# Flyfocus_Bird_CANdy_V1_0.net
KiCad netlist of a schematic drawn in EAGLE
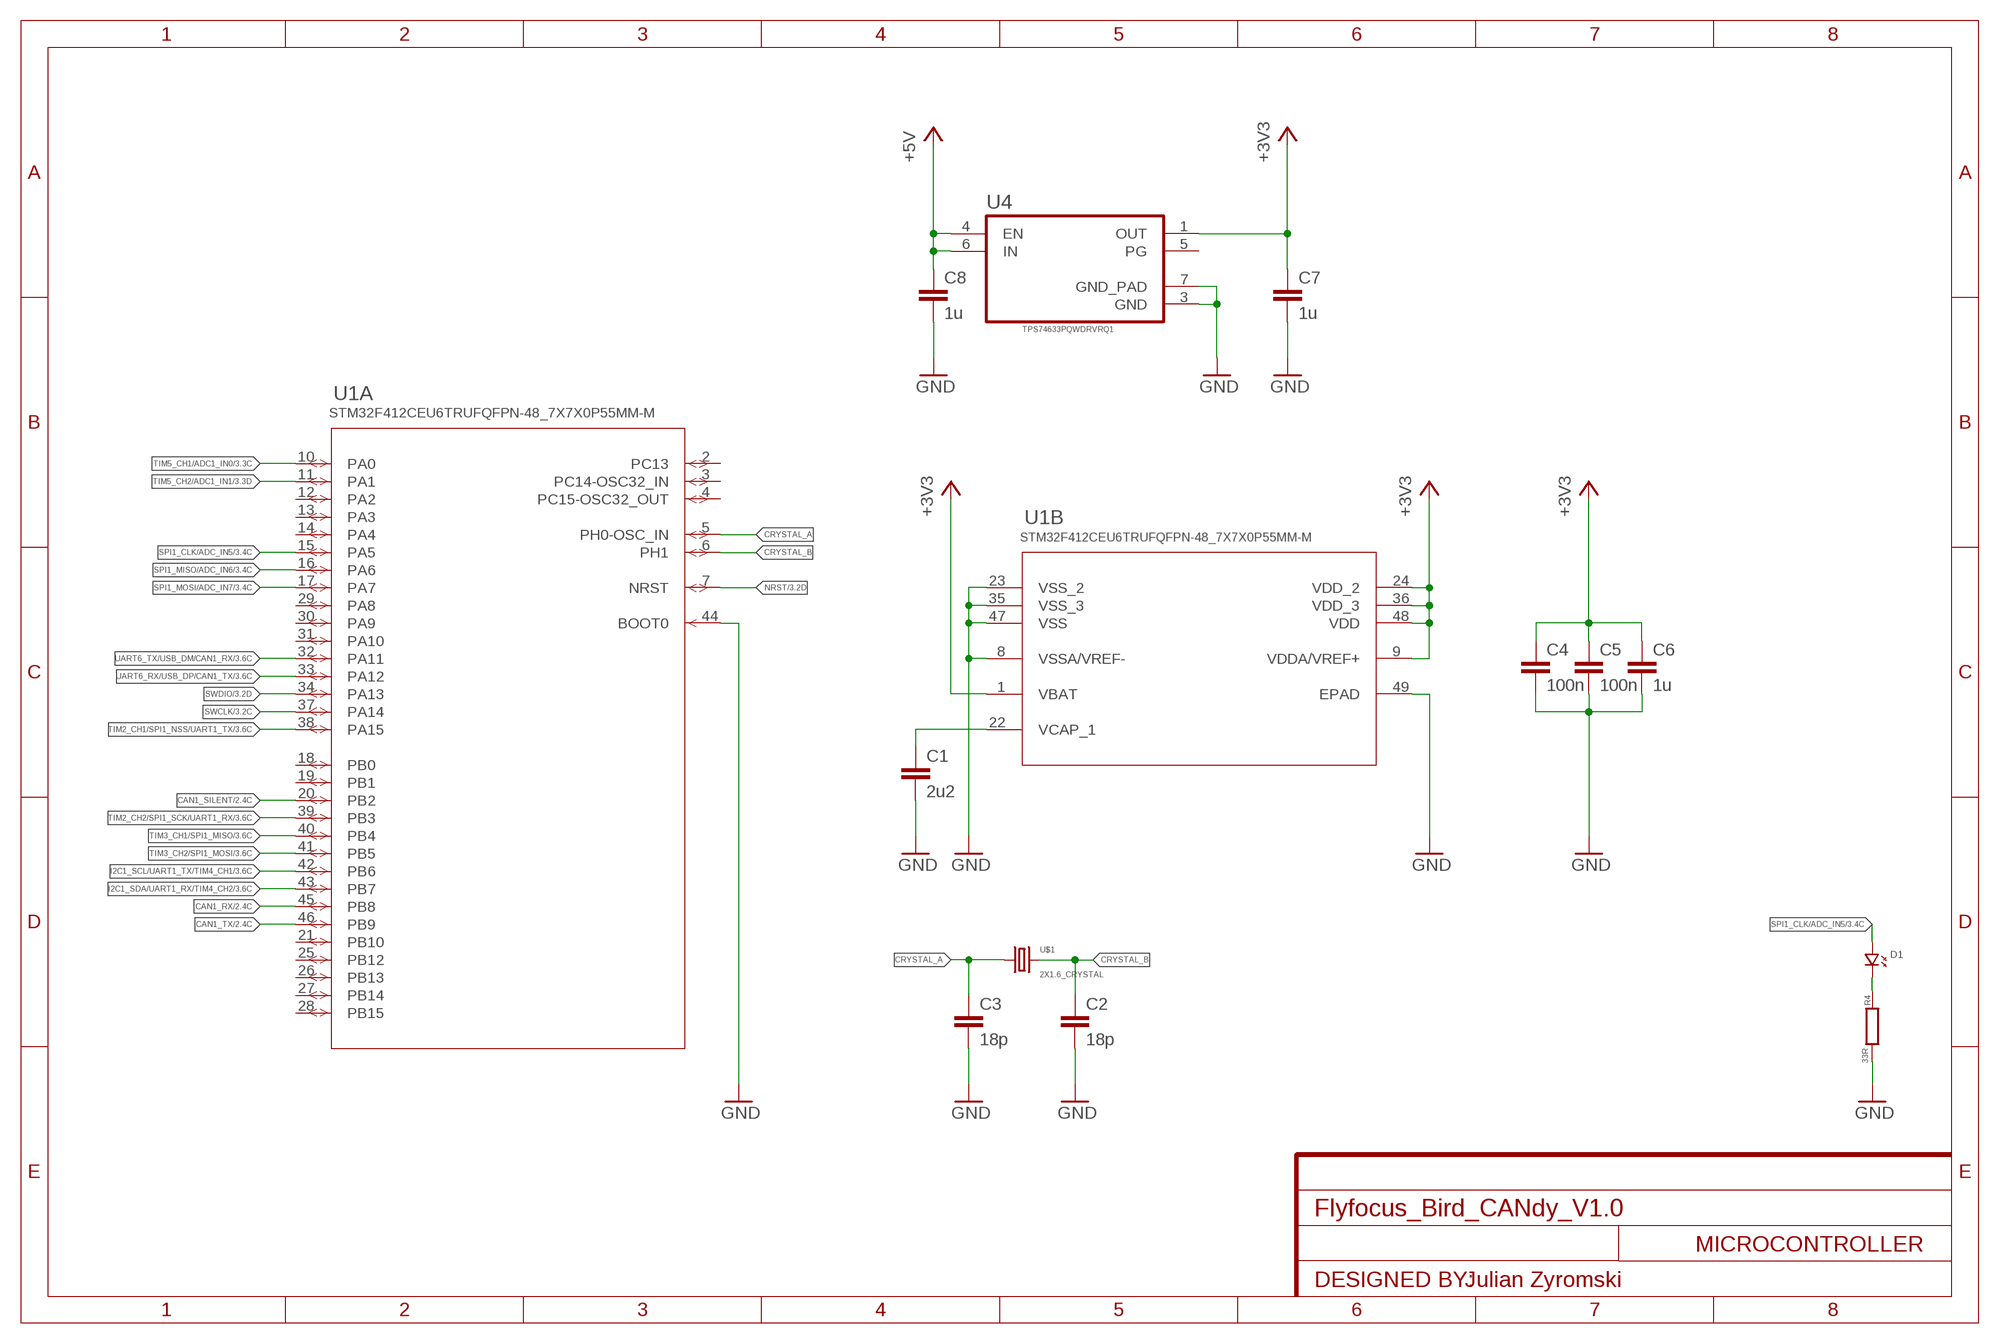
[diagram p0: schematic, sheet 1]
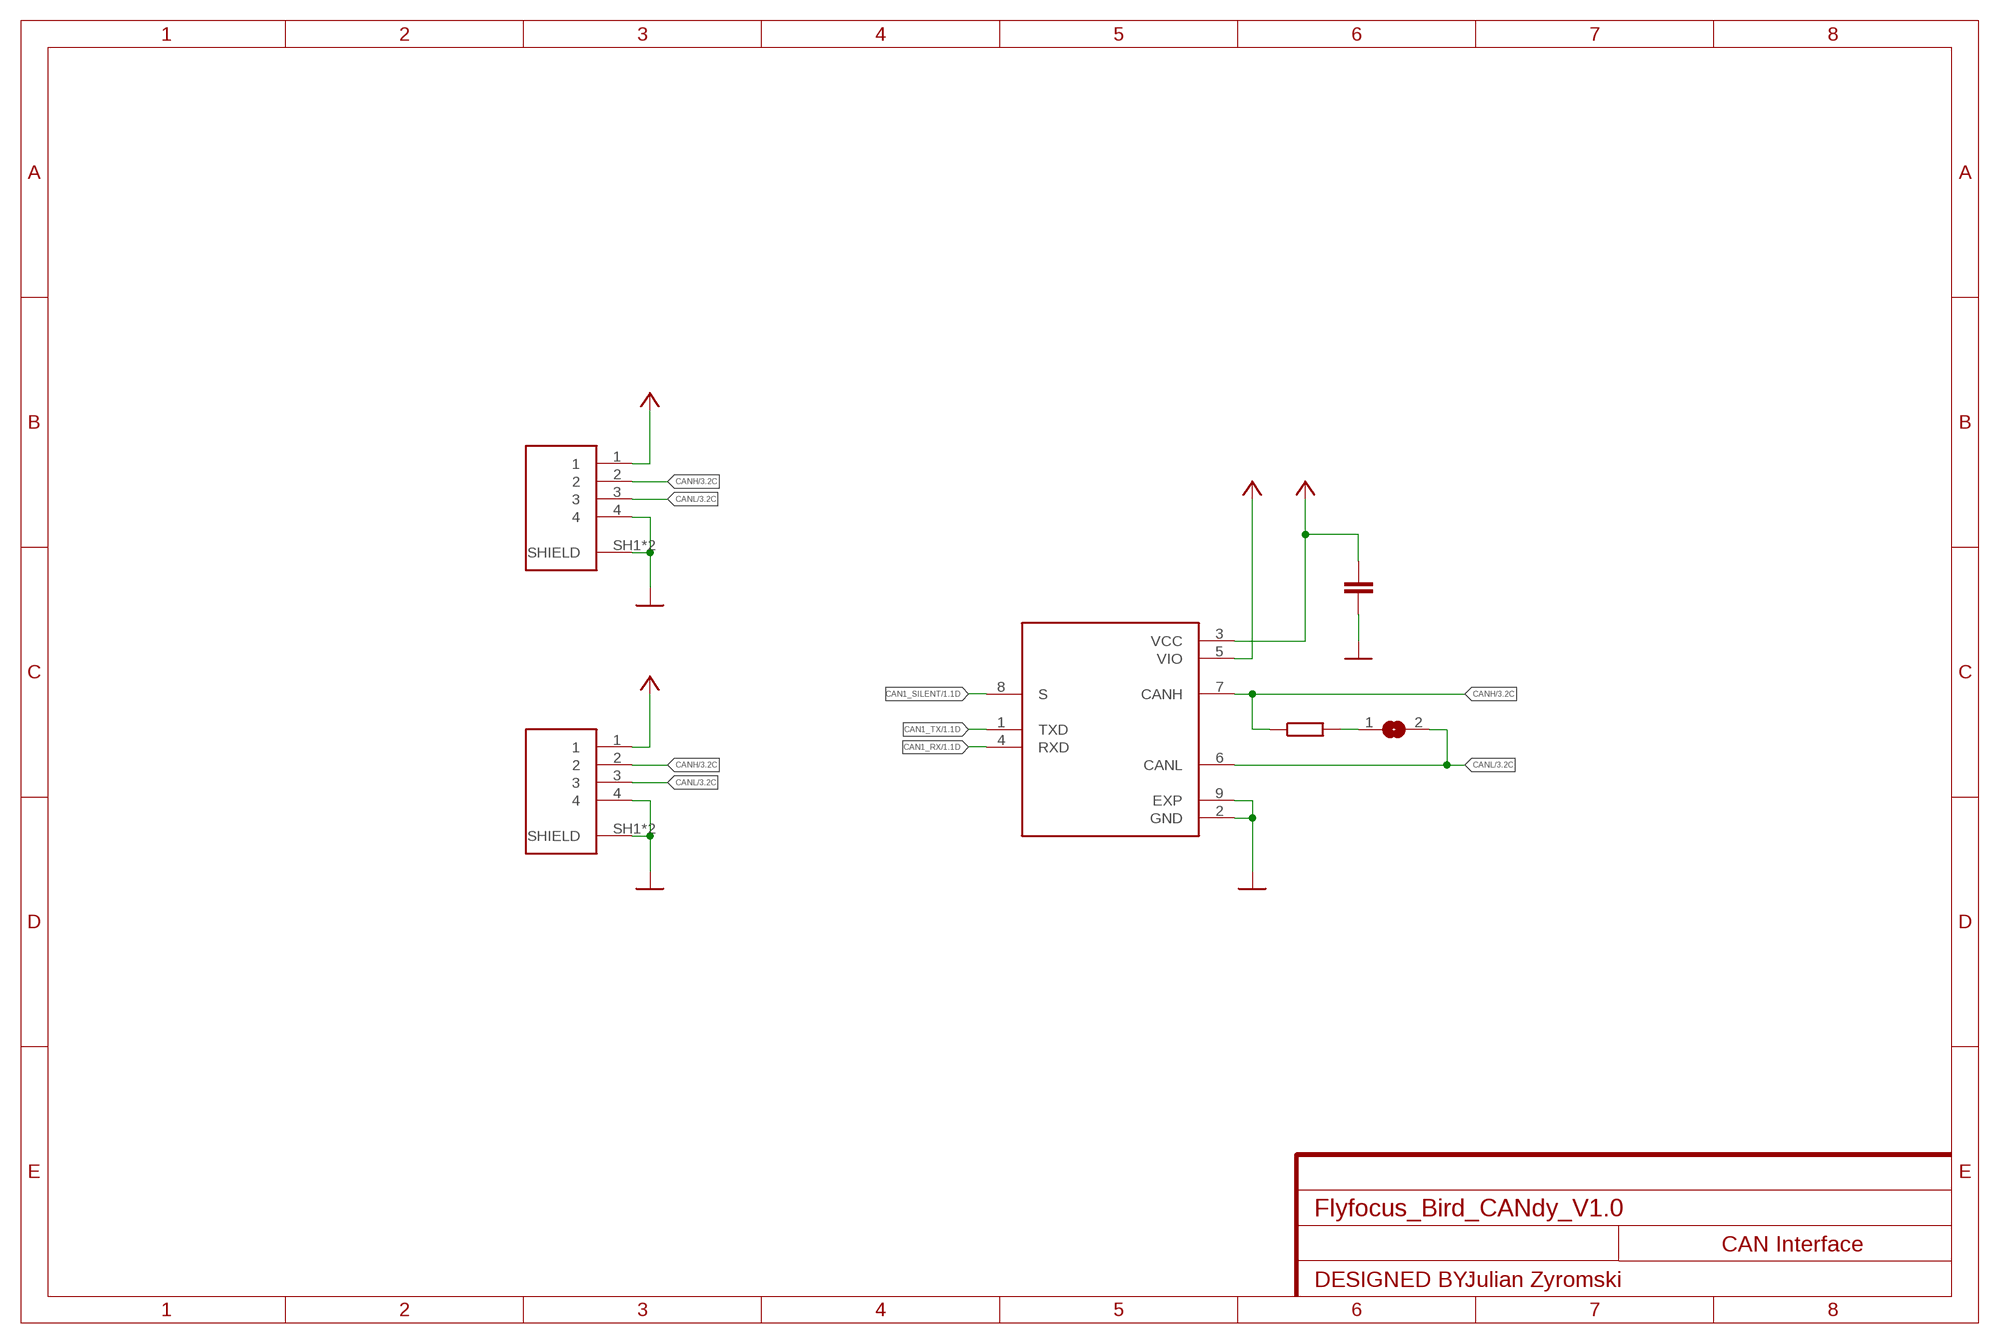
[diagram p1: schematic, sheet 2]
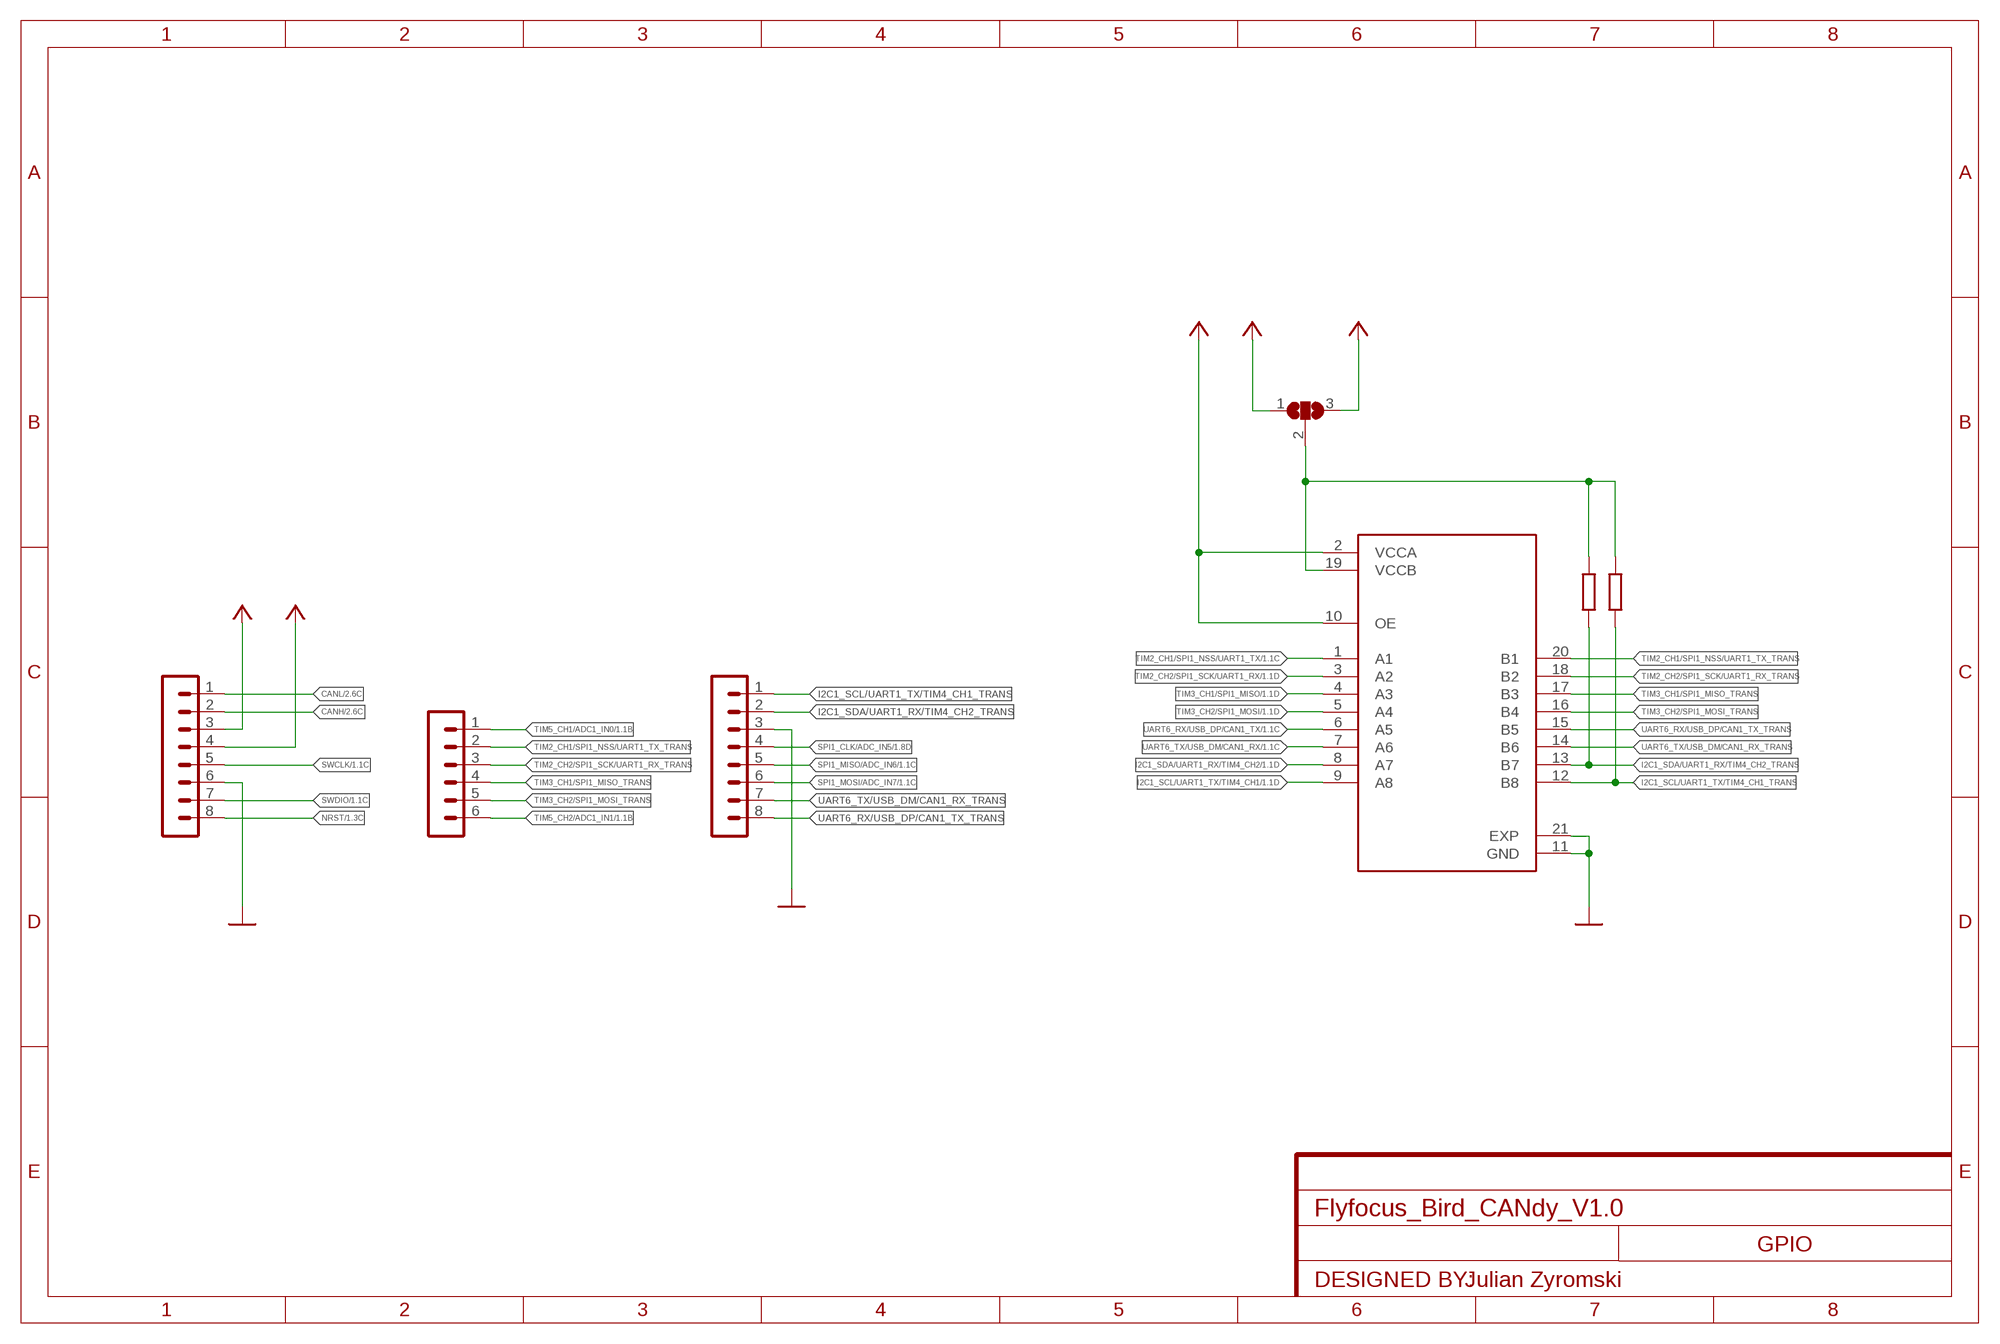
[diagram p2: schematic, sheet 3]

(export (version "E")
  (design (tool "Eeschema 10.0.6"))
  (components
    (comp (ref "C1")
      (value "2u2")
      (footprint "eagle-import:R0402")
      (libsource (lib "eagle-import") (part "C-EUC0402_RESISTOR_FOOTPRINT"))
    )
    (comp (ref "C2")
      (value "18p")
      (footprint "eagle-import:R0402")
      (libsource (lib "eagle-import") (part "C-EUC0402_RESISTOR_FOOTPRINT"))
    )
    (comp (ref "C3")
      (value "18p")
      (footprint "eagle-import:R0402")
      (libsource (lib "eagle-import") (part "C-EUC0402_RESISTOR_FOOTPRINT"))
    )
    (comp (ref "C4")
      (value "100n")
      (footprint "eagle-import:R0402")
      (libsource (lib "eagle-import") (part "C-EUC0402_RESISTOR_FOOTPRINT"))
    )
    (comp (ref "C5")
      (value "100n")
      (footprint "eagle-import:R0402")
      (libsource (lib "eagle-import") (part "C-EUC0402_RESISTOR_FOOTPRINT"))
    )
    (comp (ref "C6")
      (value "1u")
      (footprint "eagle-import:R0402")
      (libsource (lib "eagle-import") (part "C-EUC0402_RESISTOR_FOOTPRINT"))
    )
    (comp (ref "C7")
      (value "1u")
      (footprint "eagle-import:R0402")
      (libsource (lib "eagle-import") (part "C-EUC0402_RESISTOR_FOOTPRINT"))
    )
    (comp (ref "C8")
      (value "1u")
      (footprint "eagle-import:R0402")
      (libsource (lib "eagle-import") (part "C-EUC0402_RESISTOR_FOOTPRINT"))
    )
    (comp (ref "D1")
      (value "LED.0402")
      (footprint "eagle-import:0402.LED")
      (libsource (lib "eagle-import") (part "LED.0402"))
    )
    (comp (ref "R4")
      (value "33R")
      (footprint "eagle-import:R0402")
      (libsource (lib "eagle-import") (part "R-EU_R0402"))
    )
    (comp (ref "U$1")
      (value "2X1.6_CRYSTAL")
      (footprint "eagle-import:OSC_FA-128_16MHZ")
      (libsource (lib "eagle-import") (part "2X1.6_CRYSTAL"))
    )
    (comp (ref "U1")
      (value "STM32F412CEU6TRUFQFPN-48_7X7X0P55MM-M")
      (footprint "eagle-import:UFQFPN-48_7X7X0P55MM-M")
      (fields
        (field (name "MANUFACTURER_PART_NUMBER") "STM32F412CEU6TR")
        (field (name "COPYRIGHT") "Copyright (C) 2018 Accelerated Designs. All rights reserved")
      )
      (libsource (lib "eagle-import") (part "STM32F412CEU6TRUFQFPN-48_7X7X0P55MM-M"))
    )
    (comp (ref "U4")
      (value "TPS74633PQWDRVRQ1")
      (footprint "eagle-import:SON65P200X200X80-7N")
      (fields (field (name "MF") "Texas Instruments"))
      (libsource (lib "eagle-import") (part "TPS74633PQWDRVRQ1"))
    )
    (comp (ref "R2")
      (value "4k7")
      (footprint "eagle-import:R0402")
      (libsource (lib "eagle-import") (part "R-EU_R0402"))
    )
    (comp (ref "R3")
      (value "4k7")
      (footprint "eagle-import:R0402")
      (libsource (lib "eagle-import") (part "R-EU_R0402"))
    )
    (comp (ref "SJ2")
      (value "SJ2W")
      (footprint "eagle-import:SJ_2")
      (libsource (lib "eagle-import") (part "SJ2W"))
    )
    (comp (ref "SV1")
      (value "MA08-1")
      (footprint "eagle-import:MA08-1")
      (libsource (lib "eagle-import") (part "MA08-1"))
    )
    (comp (ref "SV2")
      (value "MA08-1")
      (footprint "eagle-import:MA08-1")
      (libsource (lib "eagle-import") (part "MA08-1"))
    )
    (comp (ref "SV3")
      (value "MA06-1")
      (footprint "eagle-import:MA06-1")
      (libsource (lib "eagle-import") (part "MA06-1"))
    )
    (comp (ref "U3")
      (value "TXS0108ERGYR")
      (footprint "eagle-import:IC_TXS0108ERGYR")
      (fields (field (name "MF") "Texas Instruments"))
      (libsource (lib "eagle-import") (part "TXS0108ERGYR"))
    )
    (comp (ref "C9")
      (value "2u2")
      (footprint "eagle-import:R0402")
      (libsource (lib "eagle-import") (part "C-EUC0402_RESISTOR_FOOTPRINT"))
    )
    (comp (ref "J1")
      (value "SM04B-GHS-TB(LF)(SN)-")
      (footprint "eagle-import:JST_SM04B-GHS-TB(LF)(SN)-")
      (fields (field (name "MF") "JST Sales") (field (name "MP") "SM04B-GHS-TB_LF__SN_-"))
      (libsource (lib "eagle-import") (part "SM04B-GHS-TB(LF)(SN)-"))
    )
    (comp (ref "J2")
      (value "SM04B-GHS-TB(LF)(SN)-")
      (footprint "eagle-import:JST_SM04B-GHS-TB(LF)(SN)-")
      (fields (field (name "MF") "JST Sales") (field (name "MP") "SM04B-GHS-TB_LF__SN_-"))
      (libsource (lib "eagle-import") (part "SM04B-GHS-TB(LF)(SN)-"))
    )
    (comp (ref "R1")
      (value "120R/thick_film")
      (footprint "eagle-import:0603")
      (libsource (lib "eagle-import") (part "R0603"))
    )
    (comp (ref "SJ1") (value "SJ") (footprint "eagle-import:SJ") (libsource (lib "eagle-import") (part "SJ")))
    (comp (ref "U2")
      (value "TJA1051TK/3/1J")
      (footprint "eagle-import:SON65P300X300X95-8N")
      (fields (field (name "MF") "NXP USA"))
      (libsource (lib "eagle-import") (part "TJA1051TK/3/1J"))
    )
  )
  (nets
    (net (code "1") (name "+3V3") (class "Default")
      (node (ref "C4") (pin "1") (pinfunction "1_1") (pintype "passive"))
      (node (ref "C5") (pin "1") (pinfunction "1_1") (pintype "passive"))
      (node (ref "C6") (pin "1") (pinfunction "1_1") (pintype "passive"))
      (node (ref "C7") (pin "1") (pinfunction "1_1") (pintype "passive"))
      (node (ref "SJ2") (pin "1") (pinfunction "1_1") (pintype "passive"))
      (node (ref "SV1") (pin "4") (pinfunction "4_4") (pintype "passive"))
      (node (ref "U1") (pin "1") (pinfunction "VBAT_1") (pintype "power_in"))
      (node (ref "U1") (pin "24") (pinfunction "VDD_2_24") (pintype "power_in"))
      (node (ref "U1") (pin "36") (pinfunction "VDD_3_36") (pintype "power_in"))
      (node (ref "U1") (pin "48") (pinfunction "VDD_48") (pintype "power_in"))
      (node (ref "U1") (pin "9") (pinfunction "VDDA/VREF+_9") (pintype "power_in"))
      (node (ref "U2") (pin "5") (pinfunction "VIO_5") (pintype "power_in"))
      (node (ref "U3") (pin "10") (pinfunction "OE_10") (pintype "input"))
      (node (ref "U3") (pin "2") (pinfunction "VCCA_2") (pintype "power_in"))
      (node (ref "U4") (pin "1") (pinfunction "OUT_1") (pintype "output"))
    )
    (net (code "2") (name "+5V") (class "Default")
      (node (ref "C8") (pin "1") (pinfunction "1_1") (pintype "passive"))
      (node (ref "C9") (pin "1") (pinfunction "1_1") (pintype "passive"))
      (node (ref "J1") (pin "1") (pinfunction "1_1") (pintype "passive"))
      (node (ref "J2") (pin "1") (pinfunction "1_1") (pintype "passive"))
      (node (ref "SJ2") (pin "3") (pinfunction "3_3") (pintype "passive"))
      (node (ref "SV1") (pin "3") (pinfunction "3_3") (pintype "passive"))
      (node (ref "U2") (pin "3") (pinfunction "VCC_3") (pintype "power_in"))
      (node (ref "U4") (pin "4") (pinfunction "EN_4") (pintype "input"))
      (node (ref "U4") (pin "6") (pinfunction "IN_6") (pintype "input"))
    )
    (net (code "3") (name "CAN1_RX") (class "Default")
      (node (ref "U1") (pin "45") (pinfunction "PB8_45") (pintype "bidirectional"))
      (node (ref "U2") (pin "4") (pinfunction "RXD_4") (pintype "output"))
    )
    (net (code "4") (name "CAN1_SILENT") (class "Default")
      (node (ref "U1") (pin "20") (pinfunction "PB2_20") (pintype "bidirectional"))
      (node (ref "U2") (pin "8") (pinfunction "S_8") (pintype "input"))
    )
    (net (code "5") (name "CAN1_TX") (class "Default")
      (node (ref "U1") (pin "46") (pinfunction "PB9_46") (pintype "bidirectional"))
      (node (ref "U2") (pin "1") (pinfunction "TXD_1") (pintype "input"))
    )
    (net (code "6") (name "CANH") (class "Default")
      (node (ref "J1") (pin "2") (pinfunction "2_2") (pintype "passive"))
      (node (ref "J2") (pin "2") (pinfunction "2_2") (pintype "passive"))
      (node (ref "R1") (pin "P$1") (pinfunction "1_P$1") (pintype "passive"))
      (node (ref "SV1") (pin "2") (pinfunction "2_2") (pintype "passive"))
      (node (ref "U2") (pin "7") (pinfunction "CANH_7") (pintype "bidirectional"))
    )
    (net (code "7") (name "CANL") (class "Default")
      (node (ref "J1") (pin "3") (pinfunction "3_3") (pintype "passive"))
      (node (ref "J2") (pin "3") (pinfunction "3_3") (pintype "passive"))
      (node (ref "SJ1") (pin "2") (pinfunction "2_2") (pintype "passive"))
      (node (ref "SV1") (pin "1") (pinfunction "1_1") (pintype "passive"))
      (node (ref "U2") (pin "6") (pinfunction "CANL_6") (pintype "bidirectional"))
    )
    (net (code "8") (name "CRYSTAL_A") (class "Default")
      (node (ref "C3") (pin "1") (pinfunction "1_1") (pintype "passive"))
      (node (ref "U$1") (pin "1") (pinfunction "1_1") (pintype "passive"))
      (node (ref "U1") (pin "5") (pinfunction "PH0-OSC_IN_5") (pintype "bidirectional"))
    )
    (net (code "9") (name "CRYSTAL_B") (class "Default")
      (node (ref "C2") (pin "1") (pinfunction "1_1") (pintype "passive"))
      (node (ref "U$1") (pin "3") (pinfunction "2_3") (pintype "passive"))
      (node (ref "U1") (pin "6") (pinfunction "PH1_6") (pintype "bidirectional"))
    )
    (net (code "10") (name "GND") (class "Default")
      (node (ref "C1") (pin "2") (pinfunction "2_2") (pintype "passive"))
      (node (ref "C2") (pin "2") (pinfunction "2_2") (pintype "passive"))
      (node (ref "C3") (pin "2") (pinfunction "2_2") (pintype "passive"))
      (node (ref "C4") (pin "2") (pinfunction "2_2") (pintype "passive"))
      (node (ref "C5") (pin "2") (pinfunction "2_2") (pintype "passive"))
      (node (ref "C6") (pin "2") (pinfunction "2_2") (pintype "passive"))
      (node (ref "C7") (pin "2") (pinfunction "2_2") (pintype "passive"))
      (node (ref "C8") (pin "2") (pinfunction "2_2") (pintype "passive"))
      (node (ref "C9") (pin "2") (pinfunction "2_2") (pintype "passive"))
      (node (ref "J1") (pin "4") (pinfunction "4_4") (pintype "passive"))
      (node (ref "J1") (pin "SH1") (pinfunction "SHIELD_SH1") (pintype "power_in"))
      (node (ref "J1") (pin "SH2") (pinfunction "SHIELD_SH2") (pintype "power_in"))
      (node (ref "J2") (pin "4") (pinfunction "4_4") (pintype "passive"))
      (node (ref "J2") (pin "SH1") (pinfunction "SHIELD_SH1") (pintype "power_in"))
      (node (ref "J2") (pin "SH2") (pinfunction "SHIELD_SH2") (pintype "power_in"))
      (node (ref "R4") (pin "2") (pinfunction "2_2") (pintype "passive"))
      (node (ref "SV1") (pin "6") (pinfunction "6_6") (pintype "passive"))
      (node (ref "SV2") (pin "3") (pinfunction "3_3") (pintype "passive"))
      (node (ref "U1") (pin "23") (pinfunction "VSS_2_23") (pintype "power_in"))
      (node (ref "U1") (pin "35") (pinfunction "VSS_3_35") (pintype "power_in"))
      (node (ref "U1") (pin "44") (pinfunction "BOOT0_44") (pintype "input"))
      (node (ref "U1") (pin "47") (pinfunction "VSS_47") (pintype "power_in"))
      (node (ref "U1") (pin "49") (pinfunction "EPAD_49") (pintype "passive"))
      (node (ref "U1") (pin "8") (pinfunction "VSSA/VREF-_8") (pintype "power_in"))
      (node (ref "U2") (pin "2") (pinfunction "GND_2") (pintype "power_in"))
      (node (ref "U2") (pin "9") (pinfunction "EXP_9") (pintype "power_in"))
      (node (ref "U3") (pin "11") (pinfunction "GND_11") (pintype "power_in"))
      (node (ref "U3") (pin "21") (pinfunction "EXP_21") (pintype "power_in"))
      (node (ref "U4") (pin "3") (pinfunction "GND_3") (pintype "power_in"))
      (node (ref "U4") (pin "7") (pinfunction "GND_PAD_7") (pintype "power_in"))
    )
    (net (code "11") (name "I2C1_SCL{slash}UART1_TX{slash}TIM4_CH1") (class "Default")
      (node (ref "U1") (pin "42") (pinfunction "PB6_42") (pintype "bidirectional"))
      (node (ref "U3") (pin "9") (pinfunction "A8_9") (pintype "bidirectional"))
    )
    (net (code "12") (name "I2C1_SCL{slash}UART1_TX{slash}TIM4_CH1_TRANS") (class "Default")
      (node (ref "R3") (pin "1") (pinfunction "1_1") (pintype "passive"))
      (node (ref "SV2") (pin "1") (pinfunction "1_1") (pintype "passive"))
      (node (ref "U3") (pin "12") (pinfunction "B8_12") (pintype "bidirectional"))
    )
    (net (code "13") (name "I2C1_SDA{slash}UART1_RX{slash}TIM4_CH2") (class "Default")
      (node (ref "U1") (pin "43") (pinfunction "PB7_43") (pintype "bidirectional"))
      (node (ref "U3") (pin "8") (pinfunction "A7_8") (pintype "bidirectional"))
    )
    (net (code "14") (name "I2C1_SDA{slash}UART1_RX{slash}TIM4_CH2_TRANS") (class "Default")
      (node (ref "R2") (pin "1") (pinfunction "1_1") (pintype "passive"))
      (node (ref "SV2") (pin "2") (pinfunction "2_2") (pintype "passive"))
      (node (ref "U3") (pin "13") (pinfunction "B7_13") (pintype "bidirectional"))
    )
    (net (code "15") (name "NRST") (class "Default")
      (node (ref "SV1") (pin "8") (pinfunction "8_8") (pintype "passive"))
      (node (ref "U1") (pin "7") (pinfunction "NRST_7") (pintype "bidirectional"))
    )
    (net (code "16") (name "Net-(D1-2)") (class "Default")
      (node (ref "D1") (pin "P$2") (pinfunction "2_P$2") (pintype "bidirectional"))
      (node (ref "R4") (pin "1") (pinfunction "1_1") (pintype "passive"))
    )
    (net (code "17") (name "Net-(R1-2)") (class "Default")
      (node (ref "R1") (pin "P$2") (pinfunction "2_P$2") (pintype "passive"))
      (node (ref "SJ1") (pin "1") (pinfunction "1_1") (pintype "passive"))
    )
    (net (code "18") (name "Net-(U1B-VCAP_1)") (class "Default")
      (node (ref "C1") (pin "1") (pinfunction "1_1") (pintype "passive"))
      (node (ref "U1") (pin "22") (pinfunction "VCAP_1_22") (pintype "power_in"))
    )
    (net (code "19") (name "Net-(U3-VCCB)") (class "Default")
      (node (ref "R2") (pin "2") (pinfunction "2_2") (pintype "passive"))
      (node (ref "R3") (pin "2") (pinfunction "2_2") (pintype "passive"))
      (node (ref "SJ2") (pin "2") (pinfunction "2_2") (pintype "passive"))
      (node (ref "U3") (pin "19") (pinfunction "VCCB_19") (pintype "power_in"))
    )
    (net (code "20") (name "SPI1_CLK{slash}ADC_IN5") (class "Default")
      (node (ref "D1") (pin "P$1") (pinfunction "1_P$1") (pintype "bidirectional"))
      (node (ref "SV2") (pin "4") (pinfunction "4_4") (pintype "passive"))
      (node (ref "U1") (pin "15") (pinfunction "PA5_15") (pintype "bidirectional"))
    )
    (net (code "21") (name "SPI1_MISO{slash}ADC_IN6") (class "Default")
      (node (ref "SV2") (pin "5") (pinfunction "5_5") (pintype "passive"))
      (node (ref "U1") (pin "16") (pinfunction "PA6_16") (pintype "bidirectional"))
    )
    (net (code "22") (name "SPI1_MOSI{slash}ADC_IN7") (class "Default")
      (node (ref "SV2") (pin "6") (pinfunction "6_6") (pintype "passive"))
      (node (ref "U1") (pin "17") (pinfunction "PA7_17") (pintype "bidirectional"))
    )
    (net (code "23") (name "SWCLK") (class "Default")
      (node (ref "SV1") (pin "5") (pinfunction "5_5") (pintype "passive"))
      (node (ref "U1") (pin "37") (pinfunction "PA14_37") (pintype "bidirectional"))
    )
    (net (code "24") (name "SWDIO") (class "Default")
      (node (ref "SV1") (pin "7") (pinfunction "7_7") (pintype "passive"))
      (node (ref "U1") (pin "34") (pinfunction "PA13_34") (pintype "bidirectional"))
    )
    (net (code "25") (name "TIM2_CH1{slash}SPI1_NSS{slash}UART1_TX") (class "Default")
      (node (ref "U1") (pin "38") (pinfunction "PA15_38") (pintype "bidirectional"))
      (node (ref "U3") (pin "1") (pinfunction "A1_1") (pintype "bidirectional"))
    )
    (net (code "26") (name "TIM2_CH1{slash}SPI1_NSS{slash}UART1_TX_TRANS") (class "Default")
      (node (ref "SV3") (pin "2") (pinfunction "2_2") (pintype "passive"))
      (node (ref "U3") (pin "20") (pinfunction "B1_20") (pintype "bidirectional"))
    )
    (net (code "27") (name "TIM2_CH2{slash}SPI1_SCK{slash}UART1_RX") (class "Default")
      (node (ref "U1") (pin "39") (pinfunction "PB3_39") (pintype "bidirectional"))
      (node (ref "U3") (pin "3") (pinfunction "A2_3") (pintype "bidirectional"))
    )
    (net (code "28") (name "TIM2_CH2{slash}SPI1_SCK{slash}UART1_RX_TRANS") (class "Default")
      (node (ref "SV3") (pin "3") (pinfunction "3_3") (pintype "passive"))
      (node (ref "U3") (pin "18") (pinfunction "B2_18") (pintype "bidirectional"))
    )
    (net (code "29") (name "TIM3_CH1{slash}SPI1_MISO") (class "Default")
      (node (ref "U1") (pin "40") (pinfunction "PB4_40") (pintype "bidirectional"))
      (node (ref "U3") (pin "4") (pinfunction "A3_4") (pintype "bidirectional"))
    )
    (net (code "30") (name "TIM3_CH1{slash}SPI1_MISO_TRANS") (class "Default")
      (node (ref "SV3") (pin "4") (pinfunction "4_4") (pintype "passive"))
      (node (ref "U3") (pin "17") (pinfunction "B3_17") (pintype "bidirectional"))
    )
    (net (code "31") (name "TIM3_CH2{slash}SPI1_MOSI") (class "Default")
      (node (ref "U1") (pin "41") (pinfunction "PB5_41") (pintype "bidirectional"))
      (node (ref "U3") (pin "5") (pinfunction "A4_5") (pintype "bidirectional"))
    )
    (net (code "32") (name "TIM3_CH2{slash}SPI1_MOSI_TRANS") (class "Default")
      (node (ref "SV3") (pin "5") (pinfunction "5_5") (pintype "passive"))
      (node (ref "U3") (pin "16") (pinfunction "B4_16") (pintype "bidirectional"))
    )
    (net (code "33") (name "TIM5_CH1{slash}ADC1_IN0") (class "Default")
      (node (ref "SV3") (pin "1") (pinfunction "1_1") (pintype "passive"))
      (node (ref "U1") (pin "10") (pinfunction "PA0_10") (pintype "bidirectional"))
    )
    (net (code "34") (name "TIM5_CH2{slash}ADC1_IN1") (class "Default")
      (node (ref "SV3") (pin "6") (pinfunction "6_6") (pintype "passive"))
      (node (ref "U1") (pin "11") (pinfunction "PA1_11") (pintype "bidirectional"))
    )
    (net (code "35") (name "UART6_RX{slash}USB_DP{slash}CAN1_TX") (class "Default")
      (node (ref "U1") (pin "33") (pinfunction "PA12_33") (pintype "bidirectional"))
      (node (ref "U3") (pin "6") (pinfunction "A5_6") (pintype "bidirectional"))
    )
    (net (code "36") (name "UART6_RX{slash}USB_DP{slash}CAN1_TX_TRANS") (class "Default")
      (node (ref "SV2") (pin "8") (pinfunction "8_8") (pintype "passive"))
      (node (ref "U3") (pin "15") (pinfunction "B5_15") (pintype "bidirectional"))
    )
    (net (code "37") (name "UART6_TX{slash}USB_DM{slash}CAN1_RX") (class "Default")
      (node (ref "U1") (pin "32") (pinfunction "PA11_32") (pintype "bidirectional"))
      (node (ref "U3") (pin "7") (pinfunction "A6_7") (pintype "bidirectional"))
    )
    (net (code "38") (name "UART6_TX{slash}USB_DM{slash}CAN1_RX_TRANS") (class "Default")
      (node (ref "SV2") (pin "7") (pinfunction "7_7") (pintype "passive"))
      (node (ref "U3") (pin "14") (pinfunction "B6_14") (pintype "bidirectional"))
    )
    (net (code "39") (name "unconnected-(U1A-PA2-Pad12)") (class "Default")
      (node (ref "U1") (pin "12") (pinfunction "PA2_12") (pintype "bidirectional"))
    )
    (net (code "40") (name "unconnected-(U1A-PA3-Pad13)") (class "Default")
      (node (ref "U1") (pin "13") (pinfunction "PA3_13") (pintype "bidirectional"))
    )
    (net (code "41") (name "unconnected-(U1A-PA4-Pad14)") (class "Default")
      (node (ref "U1") (pin "14") (pinfunction "PA4_14") (pintype "bidirectional"))
    )
    (net (code "42") (name "unconnected-(U1A-PA8-Pad29)") (class "Default")
      (node (ref "U1") (pin "29") (pinfunction "PA8_29") (pintype "bidirectional"))
    )
    (net (code "43") (name "unconnected-(U1A-PA9-Pad30)") (class "Default")
      (node (ref "U1") (pin "30") (pinfunction "PA9_30") (pintype "bidirectional"))
    )
    (net (code "44") (name "unconnected-(U1A-PA10-Pad31)") (class "Default")
      (node (ref "U1") (pin "31") (pinfunction "PA10_31") (pintype "bidirectional"))
    )
    (net (code "45") (name "unconnected-(U1A-PB0-Pad18)") (class "Default")
      (node (ref "U1") (pin "18") (pinfunction "PB0_18") (pintype "bidirectional"))
    )
    (net (code "46") (name "unconnected-(U1A-PB1-Pad19)") (class "Default")
      (node (ref "U1") (pin "19") (pinfunction "PB1_19") (pintype "bidirectional"))
    )
    (net (code "47") (name "unconnected-(U1A-PB10-Pad21)") (class "Default")
      (node (ref "U1") (pin "21") (pinfunction "PB10_21") (pintype "bidirectional"))
    )
    (net (code "48") (name "unconnected-(U1A-PB12-Pad25)") (class "Default")
      (node (ref "U1") (pin "25") (pinfunction "PB12_25") (pintype "bidirectional"))
    )
    (net (code "49") (name "unconnected-(U1A-PB13-Pad26)") (class "Default")
      (node (ref "U1") (pin "26") (pinfunction "PB13_26") (pintype "bidirectional"))
    )
    (net (code "50") (name "unconnected-(U1A-PB14-Pad27)") (class "Default")
      (node (ref "U1") (pin "27") (pinfunction "PB14_27") (pintype "bidirectional"))
    )
    (net (code "51") (name "unconnected-(U1A-PB15-Pad28)") (class "Default")
      (node (ref "U1") (pin "28") (pinfunction "PB15_28") (pintype "bidirectional"))
    )
    (net (code "52") (name "unconnected-(U1A-PC13-Pad2)") (class "Default")
      (node (ref "U1") (pin "2") (pinfunction "PC13_2") (pintype "bidirectional"))
    )
    (net (code "53") (name "unconnected-(U1A-PC14-OSC32_IN-Pad3)") (class "Default")
      (node (ref "U1") (pin "3") (pinfunction "PC14-OSC32_IN_3") (pintype "bidirectional"))
    )
    (net (code "54") (name "unconnected-(U1A-PC15-OSC32_OUT-Pad4)") (class "Default")
      (node (ref "U1") (pin "4") (pinfunction "PC15-OSC32_OUT_4") (pintype "bidirectional"))
    )
    (net (code "55") (name "unconnected-(U4-PG-Pad5)") (class "Default")
      (node (ref "U4") (pin "5") (pinfunction "PG_5") (pintype "output"))
    )
  )
)
